# Multivibrator.net
KiCad netlist of a schematic drawn in EAGLE
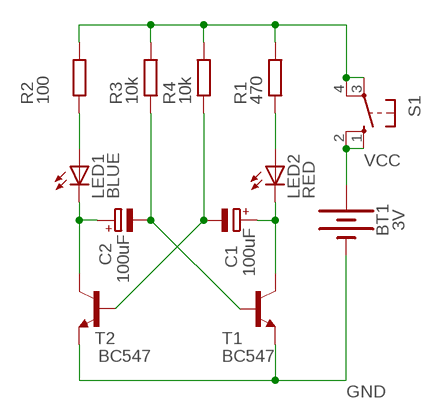
[diagram p0: schematic, sheet 1]

(export (version "E")
  (design (tool "Eeschema 10.0.6"))
  (components
    (comp (ref "BT1")
      (value "3V")
      (footprint "eagle-import:BATTCOM_20MM_PTH")
      (fields (field (name "SPICEPREFIX") "B"))
      (libsource (lib "eagle-import") (part "BATTERY-20MM_PTH"))
    )
    (comp (ref "C1")
      (value "100uF")
      (footprint "eagle-import:E2,5-5")
      (libsource (lib "eagle-import") (part "CPOL-EUE2.5-5"))
    )
    (comp (ref "C2")
      (value "100uF")
      (footprint "eagle-import:E2,5-5")
      (libsource (lib "eagle-import") (part "CPOL-EUE2.5-5"))
    )
    (comp (ref "LED1")
      (value "BLUE")
      (footprint "eagle-import:LED5MM")
      (libsource (lib "eagle-import") (part "LED5MM"))
    )
    (comp (ref "LED2")
      (value "RED")
      (footprint "eagle-import:LED5MM")
      (libsource (lib "eagle-import") (part "LED5MM"))
    )
    (comp (ref "R1")
      (value "470")
      (footprint "eagle-import:0207_10")
      (libsource (lib "eagle-import") (part "R-EU_0207/10"))
    )
    (comp (ref "R2")
      (value "100")
      (footprint "eagle-import:0207_10")
      (libsource (lib "eagle-import") (part "R-EU_0207/10"))
    )
    (comp (ref "R3")
      (value "10k")
      (footprint "eagle-import:0207_10")
      (libsource (lib "eagle-import") (part "R-EU_0207/10"))
    )
    (comp (ref "R4")
      (value "10k")
      (footprint "eagle-import:0207_10")
      (libsource (lib "eagle-import") (part "R-EU_0207/10"))
    )
    (comp (ref "S1")
      (value "10-XX")
      (footprint "eagle-import:B3F-10XX")
      (fields (field (name "MPN") "B3F-1000"))
      (libsource (lib "eagle-import") (part "10-XX"))
    )
    (comp (ref "T1")
      (value "BC547")
      (footprint "eagle-import:TO92")
      (libsource (lib "eagle-import") (part "BC547"))
    )
    (comp (ref "T2")
      (value "BC547")
      (footprint "eagle-import:TO92")
      (libsource (lib "eagle-import") (part "BC547"))
    )
  )
  (nets
    (net (code "1") (name "/GND") (class "Default")
      (node (ref "BT1") (pin "2") (pinfunction "-_2") (pintype "power_in"))
      (node (ref "T1") (pin "1") (pinfunction "E_1") (pintype "passive"))
      (node (ref "T2") (pin "1") (pinfunction "E_1") (pintype "passive"))
    )
    (net (code "2") (name "/VCC") (class "Default")
      (node (ref "R1") (pin "2") (pinfunction "2_2") (pintype "passive"))
      (node (ref "R2") (pin "2") (pinfunction "2_2") (pintype "passive"))
      (node (ref "R3") (pin "2") (pinfunction "2_2") (pintype "passive"))
      (node (ref "R4") (pin "2") (pinfunction "2_2") (pintype "passive"))
      (node (ref "S1") (pin "3") (pinfunction "P_3") (pintype "passive"))
      (node (ref "S1") (pin "4") (pinfunction "P1_4") (pintype "passive"))
    )
    (net (code "3") (name "Net-(BT1-+)") (class "Default")
      (node (ref "BT1") (pin "1") (pinfunction "+_1") (pintype "power_in"))
      (node (ref "S1") (pin "1") (pinfunction "S_1") (pintype "passive"))
      (node (ref "S1") (pin "2") (pinfunction "S1_2") (pintype "passive"))
    )
    (net (code "4") (name "Net-(LED1-C)") (class "Default")
      (node (ref "C2") (pin "+") (pinfunction "+_+") (pintype "passive"))
      (node (ref "LED1") (pin "K") (pinfunction "C_K") (pintype "passive"))
      (node (ref "T2") (pin "3") (pinfunction "C_3") (pintype "passive"))
    )
    (net (code "5") (name "Net-(LED1-PadA)") (class "Default")
      (node (ref "LED1") (pin "A") (pinfunction "A_A") (pintype "passive"))
      (node (ref "R2") (pin "1") (pinfunction "1_1") (pintype "passive"))
    )
    (net (code "6") (name "Net-(LED2-C)") (class "Default")
      (node (ref "C1") (pin "+") (pinfunction "+_+") (pintype "passive"))
      (node (ref "LED2") (pin "K") (pinfunction "C_K") (pintype "passive"))
      (node (ref "T1") (pin "3") (pinfunction "C_3") (pintype "passive"))
    )
    (net (code "7") (name "Net-(LED2-PadA)") (class "Default")
      (node (ref "LED2") (pin "A") (pinfunction "A_A") (pintype "passive"))
      (node (ref "R1") (pin "1") (pinfunction "1_1") (pintype "passive"))
    )
    (net (code "8") (name "Net-(T1-B)") (class "Default")
      (node (ref "C2") (pin "-") (pinfunction "-_-") (pintype "passive"))
      (node (ref "R3") (pin "1") (pinfunction "1_1") (pintype "passive"))
      (node (ref "T1") (pin "2") (pinfunction "B_2") (pintype "passive"))
    )
    (net (code "9") (name "Net-(T2-B)") (class "Default")
      (node (ref "C1") (pin "-") (pinfunction "-_-") (pintype "passive"))
      (node (ref "R4") (pin "1") (pinfunction "1_1") (pintype "passive"))
      (node (ref "T2") (pin "2") (pinfunction "B_2") (pintype "passive"))
    )
  )
)
